# limitSwitch.net
KiCad netlist of a schematic drawn in EAGLE
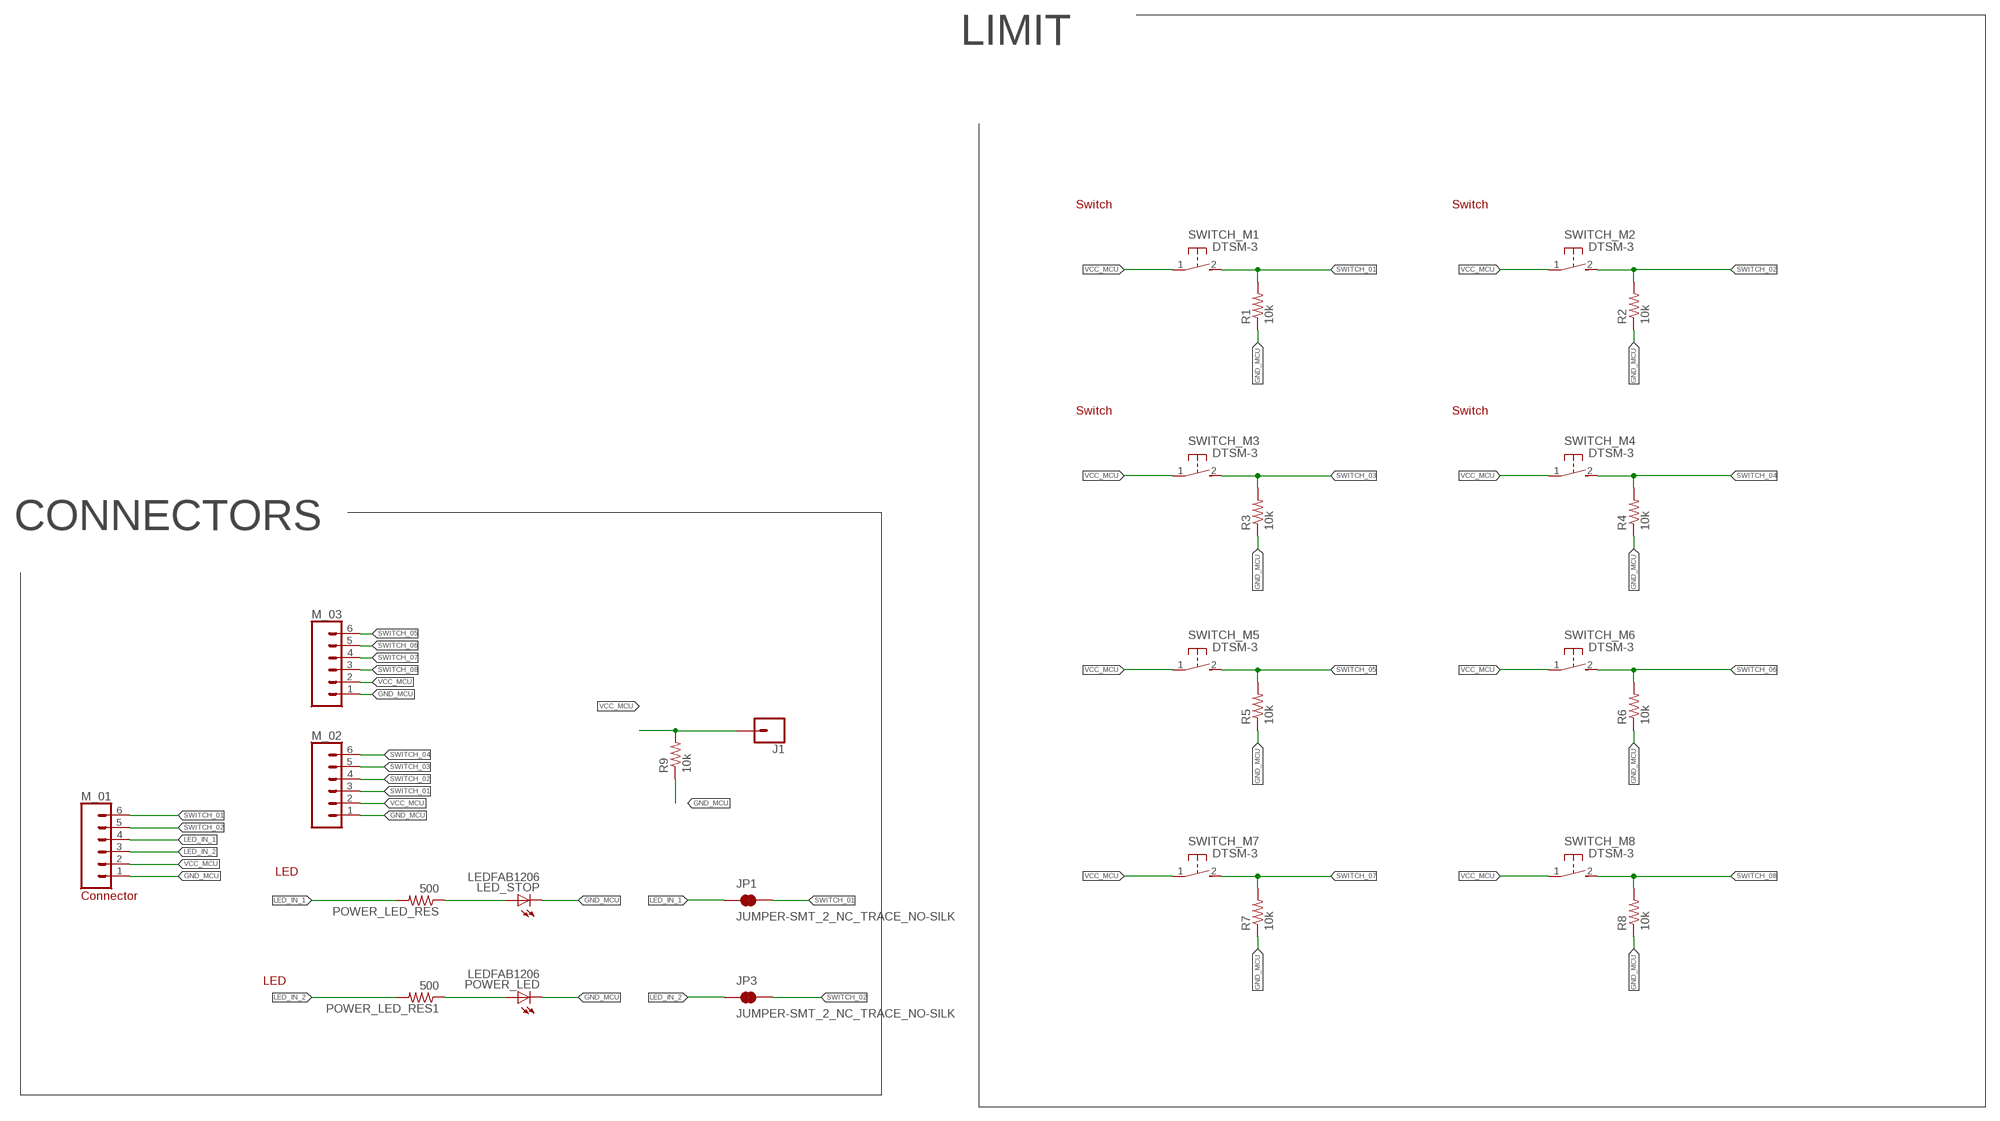
[diagram p0: schematic, sheet 1]

(export (version "E")
  (design (tool "Eeschema 10.0.6"))
  (components
    (comp (ref "J1")
      (value "CONN_01")
      (footprint "eagle-import:1X01")
      (libsource (lib "eagle-import") (part "CONN_01"))
    )
    (comp (ref "JP1")
      (value "JUMPER-SMT_2_NC_TRACE_NO-SILK")
      (footprint "eagle-import:SMT-JUMPER_2_NC_TRACE_NO-SILK")
      (libsource (lib "eagle-import") (part "JUMPER-SMT_2_NC_TRACE_NO-SILK"))
    )
    (comp (ref "JP3")
      (value "JUMPER-SMT_2_NC_TRACE_NO-SILK")
      (footprint "eagle-import:SMT-JUMPER_2_NC_TRACE_NO-SILK")
      (libsource (lib "eagle-import") (part "JUMPER-SMT_2_NC_TRACE_NO-SILK"))
    )
    (comp (ref "LED_STOP")
      (value "LEDFAB1206")
      (footprint "eagle-import:LED1206FAB")
      (libsource (lib "eagle-import") (part "LEDFAB1206"))
    )
    (comp (ref "M_01")
      (value "CONN_06SMD-1MM")
      (footprint "eagle-import:1X06-1MM")
      (libsource (lib "eagle-import") (part "CONN_06SMD-1MM"))
    )
    (comp (ref "M_02")
      (value "CONN_06SMD-1MM")
      (footprint "eagle-import:1X06-1MM")
      (libsource (lib "eagle-import") (part "CONN_06SMD-1MM"))
    )
    (comp (ref "M_03")
      (value "CONN_06SMD-1MM")
      (footprint "eagle-import:1X06-1MM")
      (libsource (lib "eagle-import") (part "CONN_06SMD-1MM"))
    )
    (comp (ref "POWER_LED")
      (value "LEDFAB1206")
      (footprint "eagle-import:LED1206FAB")
      (libsource (lib "eagle-import") (part "LEDFAB1206"))
    )
    (comp (ref "POWER_LED_RES")
      (value "500")
      (footprint "eagle-import:M0805")
      (libsource (lib "eagle-import") (part "R-US_M0805"))
    )
    (comp (ref "POWER_LED_RES1")
      (value "500")
      (footprint "eagle-import:M0805")
      (libsource (lib "eagle-import") (part "R-US_M0805"))
    )
    (comp (ref "R1")
      (value "10k")
      (footprint "eagle-import:M0805")
      (libsource (lib "eagle-import") (part "R-US_M0805"))
    )
    (comp (ref "R2")
      (value "10k")
      (footprint "eagle-import:M0805")
      (libsource (lib "eagle-import") (part "R-US_M0805"))
    )
    (comp (ref "R3")
      (value "10k")
      (footprint "eagle-import:M0805")
      (libsource (lib "eagle-import") (part "R-US_M0805"))
    )
    (comp (ref "R4")
      (value "10k")
      (footprint "eagle-import:M0805")
      (libsource (lib "eagle-import") (part "R-US_M0805"))
    )
    (comp (ref "R5")
      (value "10k")
      (footprint "eagle-import:M0805")
      (libsource (lib "eagle-import") (part "R-US_M0805"))
    )
    (comp (ref "R6")
      (value "10k")
      (footprint "eagle-import:M0805")
      (libsource (lib "eagle-import") (part "R-US_M0805"))
    )
    (comp (ref "R7")
      (value "10k")
      (footprint "eagle-import:M0805")
      (libsource (lib "eagle-import") (part "R-US_M0805"))
    )
    (comp (ref "R8")
      (value "10k")
      (footprint "eagle-import:M0805")
      (libsource (lib "eagle-import") (part "R-US_M0805"))
    )
    (comp (ref "R9")
      (value "10k")
      (footprint "eagle-import:M0805")
      (libsource (lib "eagle-import") (part "R-US_M0805"))
    )
    (comp (ref "SWITCH_M1")
      (value "DTSM-3")
      (footprint "eagle-import:DTSM-3")
      (libsource (lib "eagle-import") (part "DTSM-3"))
    )
    (comp (ref "SWITCH_M2")
      (value "DTSM-3")
      (footprint "eagle-import:DTSM-3")
      (libsource (lib "eagle-import") (part "DTSM-3"))
    )
    (comp (ref "SWITCH_M3")
      (value "DTSM-3")
      (footprint "eagle-import:DTSM-3")
      (libsource (lib "eagle-import") (part "DTSM-3"))
    )
    (comp (ref "SWITCH_M4")
      (value "DTSM-3")
      (footprint "eagle-import:DTSM-3")
      (libsource (lib "eagle-import") (part "DTSM-3"))
    )
    (comp (ref "SWITCH_M5")
      (value "DTSM-3")
      (footprint "eagle-import:DTSM-3")
      (libsource (lib "eagle-import") (part "DTSM-3"))
    )
    (comp (ref "SWITCH_M6")
      (value "DTSM-3")
      (footprint "eagle-import:DTSM-3")
      (libsource (lib "eagle-import") (part "DTSM-3"))
    )
    (comp (ref "SWITCH_M7")
      (value "DTSM-3")
      (footprint "eagle-import:DTSM-3")
      (libsource (lib "eagle-import") (part "DTSM-3"))
    )
    (comp (ref "SWITCH_M8")
      (value "DTSM-3")
      (footprint "eagle-import:DTSM-3")
      (libsource (lib "eagle-import") (part "DTSM-3"))
    )
  )
  (nets
    (net (code "1") (name "GND_MCU") (class "Default")
      (node (ref "LED_STOP") (pin "2") (pinfunction "C_2") (pintype "passive"))
      (node (ref "M_01") (pin "1") (pinfunction "1_1") (pintype "passive"))
      (node (ref "M_02") (pin "1") (pinfunction "1_1") (pintype "passive"))
      (node (ref "M_03") (pin "1") (pinfunction "1_1") (pintype "passive"))
      (node (ref "POWER_LED") (pin "2") (pinfunction "C_2") (pintype "passive"))
      (node (ref "R1") (pin "1") (pinfunction "1_1") (pintype "passive"))
      (node (ref "R2") (pin "1") (pinfunction "1_1") (pintype "passive"))
      (node (ref "R3") (pin "1") (pinfunction "1_1") (pintype "passive"))
      (node (ref "R4") (pin "1") (pinfunction "1_1") (pintype "passive"))
      (node (ref "R5") (pin "1") (pinfunction "1_1") (pintype "passive"))
      (node (ref "R6") (pin "1") (pinfunction "1_1") (pintype "passive"))
      (node (ref "R7") (pin "1") (pinfunction "1_1") (pintype "passive"))
      (node (ref "R8") (pin "1") (pinfunction "1_1") (pintype "passive"))
      (node (ref "R9") (pin "1") (pinfunction "1_1") (pintype "passive"))
    )
    (net (code "2") (name "LED_IN_1") (class "Default")
      (node (ref "JP1") (pin "1") (pinfunction "1_1") (pintype "passive"))
      (node (ref "M_01") (pin "4") (pinfunction "4_4") (pintype "passive"))
      (node (ref "POWER_LED_RES") (pin "2") (pinfunction "2_2") (pintype "passive"))
    )
    (net (code "3") (name "LED_IN_2") (class "Default")
      (node (ref "JP3") (pin "1") (pinfunction "1_1") (pintype "passive"))
      (node (ref "M_01") (pin "3") (pinfunction "3_3") (pintype "passive"))
      (node (ref "POWER_LED_RES1") (pin "2") (pinfunction "2_2") (pintype "passive"))
    )
    (net (code "4") (name "Net-(LED_STOP-A)") (class "Default")
      (node (ref "LED_STOP") (pin "1") (pinfunction "A_1") (pintype "passive"))
      (node (ref "POWER_LED_RES") (pin "1") (pinfunction "1_1") (pintype "passive"))
    )
    (net (code "5") (name "Net-(POWER_LED-A)") (class "Default")
      (node (ref "POWER_LED") (pin "1") (pinfunction "A_1") (pintype "passive"))
      (node (ref "POWER_LED_RES1") (pin "1") (pinfunction "1_1") (pintype "passive"))
    )
    (net (code "6") (name "SWITCH_01") (class "Default")
      (node (ref "JP1") (pin "2") (pinfunction "2_2") (pintype "passive"))
      (node (ref "M_01") (pin "6") (pinfunction "6_6") (pintype "passive"))
      (node (ref "M_02") (pin "3") (pinfunction "3_3") (pintype "passive"))
      (node (ref "R1") (pin "2") (pinfunction "2_2") (pintype "passive"))
      (node (ref "SWITCH_M1") (pin "2") (pinfunction "2_2") (pintype "passive"))
    )
    (net (code "7") (name "SWITCH_02") (class "Default")
      (node (ref "JP3") (pin "2") (pinfunction "2_2") (pintype "passive"))
      (node (ref "M_01") (pin "5") (pinfunction "5_5") (pintype "passive"))
      (node (ref "M_02") (pin "4") (pinfunction "4_4") (pintype "passive"))
      (node (ref "R2") (pin "2") (pinfunction "2_2") (pintype "passive"))
      (node (ref "SWITCH_M2") (pin "2") (pinfunction "2_2") (pintype "passive"))
    )
    (net (code "8") (name "SWITCH_03") (class "Default")
      (node (ref "M_02") (pin "5") (pinfunction "5_5") (pintype "passive"))
      (node (ref "R3") (pin "2") (pinfunction "2_2") (pintype "passive"))
      (node (ref "SWITCH_M3") (pin "2") (pinfunction "2_2") (pintype "passive"))
    )
    (net (code "9") (name "SWITCH_04") (class "Default")
      (node (ref "M_02") (pin "6") (pinfunction "6_6") (pintype "passive"))
      (node (ref "R4") (pin "2") (pinfunction "2_2") (pintype "passive"))
      (node (ref "SWITCH_M4") (pin "2") (pinfunction "2_2") (pintype "passive"))
    )
    (net (code "10") (name "SWITCH_05") (class "Default")
      (node (ref "M_03") (pin "6") (pinfunction "6_6") (pintype "passive"))
      (node (ref "R5") (pin "2") (pinfunction "2_2") (pintype "passive"))
      (node (ref "SWITCH_M5") (pin "2") (pinfunction "2_2") (pintype "passive"))
    )
    (net (code "11") (name "SWITCH_06") (class "Default")
      (node (ref "M_03") (pin "5") (pinfunction "5_5") (pintype "passive"))
      (node (ref "R6") (pin "2") (pinfunction "2_2") (pintype "passive"))
      (node (ref "SWITCH_M6") (pin "2") (pinfunction "2_2") (pintype "passive"))
    )
    (net (code "12") (name "SWITCH_07") (class "Default")
      (node (ref "M_03") (pin "4") (pinfunction "4_4") (pintype "passive"))
      (node (ref "R7") (pin "2") (pinfunction "2_2") (pintype "passive"))
      (node (ref "SWITCH_M7") (pin "2") (pinfunction "2_2") (pintype "passive"))
    )
    (net (code "13") (name "SWITCH_08") (class "Default")
      (node (ref "M_03") (pin "3") (pinfunction "3_3") (pintype "passive"))
      (node (ref "R8") (pin "2") (pinfunction "2_2") (pintype "passive"))
      (node (ref "SWITCH_M8") (pin "2") (pinfunction "2_2") (pintype "passive"))
    )
    (net (code "14") (name "VCC_MCU") (class "Default")
      (node (ref "J1") (pin "1") (pinfunction "1_1") (pintype "passive"))
      (node (ref "M_01") (pin "2") (pinfunction "2_2") (pintype "passive"))
      (node (ref "M_02") (pin "2") (pinfunction "2_2") (pintype "passive"))
      (node (ref "M_03") (pin "2") (pinfunction "2_2") (pintype "passive"))
      (node (ref "R9") (pin "2") (pinfunction "2_2") (pintype "passive"))
      (node (ref "SWITCH_M1") (pin "1") (pinfunction "1_1") (pintype "passive"))
      (node (ref "SWITCH_M2") (pin "1") (pinfunction "1_1") (pintype "passive"))
      (node (ref "SWITCH_M3") (pin "1") (pinfunction "1_1") (pintype "passive"))
      (node (ref "SWITCH_M4") (pin "1") (pinfunction "1_1") (pintype "passive"))
      (node (ref "SWITCH_M5") (pin "1") (pinfunction "1_1") (pintype "passive"))
      (node (ref "SWITCH_M6") (pin "1") (pinfunction "1_1") (pintype "passive"))
      (node (ref "SWITCH_M7") (pin "1") (pinfunction "1_1") (pintype "passive"))
      (node (ref "SWITCH_M8") (pin "1") (pinfunction "1_1") (pintype "passive"))
    )
  )
)
